# 36V_Supply.net
KiCad netlist of a schematic drawn in Altium Designer
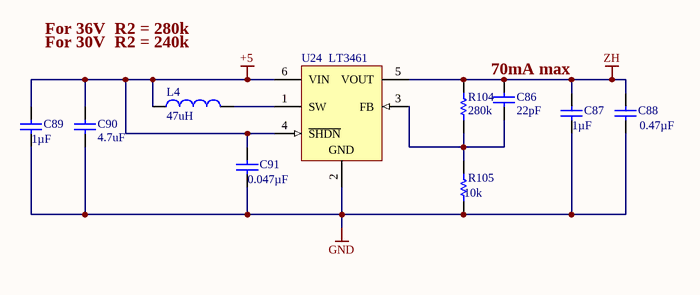
[diagram p0: 36V_Supply.SchDoc]

(export (version "E")
  (design (tool "Eeschema 10.0.6"))
  (components
    (comp (ref "C86")
      (value "22pF")
      (footprint "CAPC1206(3216)170_L")
      (description "CAP CER 22PF 50V C0G/NP0 1206")
      (fields
        (field (name "MANUFACTURER") "KEMET")
        (field (name "MANUFACTURER PART NUMBER") "C1206C220K5GACTU")
      )
      (libsource (lib "Altium Content Vault") (part "CMP-1037-04573-1"))
    )
    (comp (ref "C87")
      (value "CAP CER 1UF 50V X7R 1210")
      (footprint "CAPC1210(3225)100_N")
      (fields
        (field (name "MANUFACTURER") "Taiyo Yuden")
        (field (name "MANUFACTURER PART NUMBER") "UMK325B7105KH-T")
        (field (name "CAPACITANCE") "1µF")
        (field (name "TOLERANCE") "±10%")
      )
      (libsource (lib "Altium Content Vault") (part "CMP-1038-01123-1"))
    )
    (comp (ref "C88")
      (value "CAP CER 0.47UF 50V X7R 1206")
      (footprint "CAPC1206(3216)190_N")
      (fields
        (field (name "MANUFACTURER") "Taiyo Yuden")
        (field (name "MANUFACTURER PART NUMBER") "UMK316B7474KL-T")
        (field (name "CAPACITANCE") "0.47µF")
        (field (name "TOLERANCE") "±10%")
      )
      (libsource (lib "Altium Content Vault") (part "CMP-1037-04570-1"))
    )
    (comp (ref "C89")
      (value "CAP CER 1UF 16V X7R 0805")
      (footprint "CAPC0805(2012)145_N")
      (fields
        (field (name "MANUFACTURER") "Taiyo Yuden")
        (field (name "MANUFACTURER PART NUMBER") "EMK212B7105KG-T")
        (field (name "CAPACITANCE") "1µF")
        (field (name "TOLERANCE") "±10%")
      )
      (libsource (lib "Altium Content Vault") (part "CMP-1036-04795-1"))
    )
    (comp (ref "C90")
      (value "4.7uF")
      (footprint "CAPC0805(2012)145_M")
      (description "CAP CER 4.7UF 16V X7R 0805")
      (fields
        (field (name "MANUFACTURER") "KEMET")
        (field (name "MANUFACTURER PART NUMBER") "C0805C475K4RACTU")
      )
      (libsource (lib "Altium Content Vault") (part "CMP-1036-04750-1"))
    )
    (comp (ref "C91")
      (value "CAP CER 0.047UF 16V X7R 0603")
      (footprint "CAPC0805(2012)145_N")
      (fields
        (field (name "MANUFACTURER") "Murata Electronics North America")
        (field (name "MANUFACTURER PART NUMBER") "GRM188R71C473KA01D")
        (field (name "CAPACITANCE") "0.047µF")
        (field (name "TOLERANCE") "±10%")
      )
      (libsource (lib "Altium Content Vault") (part "CMP-1036-04795-1"))
    )
    (comp (ref "L4")
      (value "47uH")
      (footprint "C1210")
      (description "FIXED IND 47UH 170MA 1.3 OHM SMD")
      (fields
        (field (name "MANUFACTURER") "Murata Electronics North America")
        (field (name "MANUFACTURER PART NUMBER") "LQH32CN470K23L")
      )
      (libsource (lib "Miscellaneous Devices") (part "Inductor"))
    )
    (comp (ref "R104")
      (value "RES SMD 280K OHM 1% 1/8W 0805")
      (footprint "RESC0805(2012)_M")
      (fields
        (field (name "MANUFACTURER") "Vishay Dale")
        (field (name "MANUFACTURER PART NUMBER") "CRCW0805280KFKEA")
        (field (name "RESISTANCE (OHMS)") "280k")
        (field (name "TOLERANCE") "±1%")
      )
      (libsource (lib "Altium Content Vault") (part "CMP-1013-00017-1"))
    )
    (comp (ref "R105")
      (value "RES SMD 10K OHM 1% 1/8W 0805")
      (footprint "RESC0805(2012)_M")
      (fields
        (field (name "MANUFACTURER") "Yageo")
        (field (name "MANUFACTURER PART NUMBER") "RC0805FR-0710KL")
        (field (name "RESISTANCE (OHMS)") "10k")
        (field (name "TOLERANCE") "±1%")
      )
      (libsource (lib "Altium Content Vault") (part "CMP-1013-00017-1"))
    )
    (comp (ref "U24")
      (value "LT3461")
      (footprint "LT-S6-6-TSOT-23_N")
      (description "IC REG BOOST ADJ 0.3A TSOT23-6")
      (libsource (lib "Altium Content Vault") (part "CMP-0491-01698-1"))
    )
  )
  (nets
    (net (code "1") (name "+5") (class "Default")
      (node (ref "C89") (pin "2") (pinfunction "2_2") (pintype "passive"))
      (node (ref "C90") (pin "2") (pinfunction "2_2") (pintype "passive"))
      (node (ref "C91") (pin "2") (pinfunction "2_2") (pintype "passive"))
      (node (ref "L4") (pin "1") (pinfunction "1_1") (pintype "passive"))
      (node (ref "U24") (pin "4") (pinfunction "~{SHDN}_4") (pintype "input"))
      (node (ref "U24") (pin "6") (pinfunction "VIN_6") (pintype "power_in"))
    )
    (net (code "2") (name "GND") (class "Default")
      (node (ref "C87") (pin "1") (pinfunction "1_1") (pintype "passive"))
      (node (ref "C88") (pin "1") (pinfunction "1_1") (pintype "passive"))
      (node (ref "C89") (pin "1") (pinfunction "1_1") (pintype "passive"))
      (node (ref "C90") (pin "1") (pinfunction "1_1") (pintype "passive"))
      (node (ref "C91") (pin "1") (pinfunction "1_1") (pintype "passive"))
      (node (ref "R105") (pin "2") (pinfunction "2_2") (pintype "passive"))
      (node (ref "U24") (pin "2") (pinfunction "GND_2") (pintype "power_in"))
    )
    (net (code "3") (name "Net-(U24-FB)") (class "Default")
      (node (ref "C86") (pin "1") (pinfunction "1_1") (pintype "passive"))
      (node (ref "R104") (pin "2") (pinfunction "2_2") (pintype "passive"))
      (node (ref "R105") (pin "1") (pinfunction "1_1") (pintype "passive"))
      (node (ref "U24") (pin "3") (pinfunction "FB_3") (pintype "input"))
    )
    (net (code "4") (name "Net-(U24-SW)") (class "Default")
      (node (ref "L4") (pin "2") (pinfunction "2_2") (pintype "passive"))
      (node (ref "U24") (pin "1") (pinfunction "SW_1") (pintype "passive"))
    )
    (net (code "5") (name "ZH") (class "Default")
      (node (ref "C86") (pin "2") (pinfunction "2_2") (pintype "passive"))
      (node (ref "C87") (pin "2") (pinfunction "2_2") (pintype "passive"))
      (node (ref "C88") (pin "2") (pinfunction "2_2") (pintype "passive"))
      (node (ref "R104") (pin "1") (pinfunction "1_1") (pintype "passive"))
      (node (ref "U24") (pin "5") (pinfunction "VOUT_5") (pintype "power_in"))
    )
  )
)
